# Embebidos.net
KiCad netlist of a schematic drawn in Altium Designer
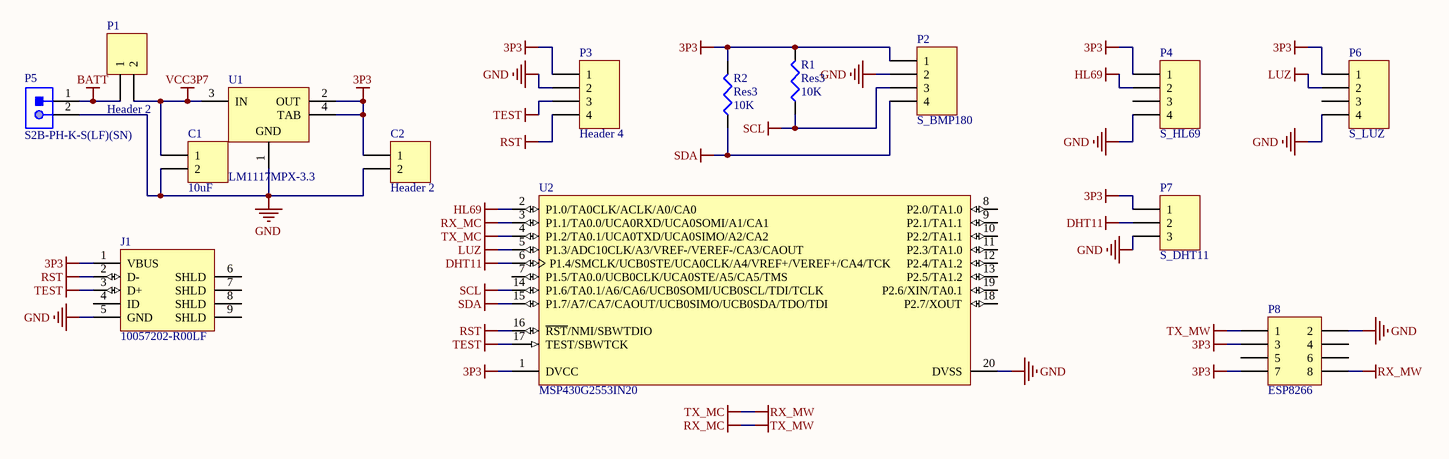
[diagram p0: Embebidos.SchDoc]

(export (version "E")
  (design (tool "Eeschema 10.0.6"))
  (components
    (comp (ref "C1")
      (value "10uF")
      (footprint "HDR1X2")
      (description "Header, 2-Pin")
      (fields (field (name "PUBLISHER") "Altium Limited"))
      (libsource (lib "Miscellaneous Connectors") (part "Header 2"))
    )
    (comp (ref "C2")
      (value "Header 2")
      (footprint "HDR1X2")
      (description "Header, 2-Pin")
      (fields (field (name "PUBLISHER") "Altium Limited"))
      (libsource (lib "Miscellaneous Connectors") (part "Header 2"))
    )
    (comp (ref "J1")
      (value "10057202-R00LF")
      (footprint "FCI-10057202-R00LF_V")
      (description "Connector Mini USB, Right Angle, Receptacle, Type B")
      (fields (field (name "MANUFACTURER") "FCI Electronics"))
      (libsource (lib "Altium Content Vault") (part "CMP-0397-00001-1"))
    )
    (comp (ref "P1")
      (value "Header 2")
      (footprint "HDR1X2")
      (description "Header, 2-Pin")
      (fields (field (name "PUBLISHER") "Altium Limited"))
      (libsource (lib "") (part "Header 2_1"))
    )
    (comp (ref "P2")
      (value "S_BMP180")
      (footprint "HDR1X4")
      (description "Header, 4-Pin")
      (fields (field (name "PUBLISHER") "Altium Limited"))
      (libsource (lib "Miscellaneous Connectors") (part "Header 4"))
    )
    (comp (ref "P3")
      (value "Header 4")
      (footprint "HDR1X4")
      (description "Header, 4-Pin")
      (fields (field (name "PUBLISHER") "Altium Limited"))
      (libsource (lib "Miscellaneous Connectors") (part "Header 4"))
    )
    (comp (ref "P4")
      (value "S_HL69")
      (footprint "HDR1X4")
      (description "Header, 4-Pin")
      (fields (field (name "PUBLISHER") "Altium Limited"))
      (libsource (lib "Miscellaneous Connectors") (part "Header 4"))
    )
    (comp (ref "P5")
      (value "S2B-PH-K-S(LF)(SN)")
      (footprint "JST-S2B-PH-K-S_V")
      (fields (field (name "TOLERANCE") "20%"))
      (libsource (lib "Altium Content Vault") (part "CMP-1755-00004-1"))
    )
    (comp (ref "P6")
      (value "S_LUZ")
      (footprint "HDR1X4")
      (description "Header, 4-Pin")
      (fields (field (name "PUBLISHER") "Altium Limited"))
      (libsource (lib "Miscellaneous Connectors") (part "Header 4"))
    )
    (comp (ref "P7")
      (value "S_DHT11")
      (footprint "HDR1X3")
      (description "Header, 3-Pin")
      (fields (field (name "PUBLISHER") "Altium Limited"))
      (libsource (lib "Miscellaneous Connectors") (part "Header 3"))
    )
    (comp (ref "P8")
      (value "ESP8266")
      (footprint "HDR2X4")
      (description "Header, 4-Pin, Dual row")
      (fields (field (name "PUBLISHER") "Altium Limited"))
      (libsource (lib "Miscellaneous Connectors") (part "Header 4X2"))
    )
    (comp (ref "R1")
      (value "Res3")
      (footprint "J1-0603")
      (description "Resistor")
      (fields (field (name "ALTIUM_VALUE") "10K") (field (name "PUBLISHER") "Altium Limited"))
      (libsource (lib "Miscellaneous Devices") (part "Res3"))
    )
    (comp (ref "R2")
      (value "Res3")
      (footprint "J1-0603")
      (description "Resistor")
      (fields (field (name "ALTIUM_VALUE") "10K") (field (name "PUBLISHER") "Altium Limited"))
      (libsource (lib "Miscellaneous Devices") (part "Res3"))
    )
    (comp (ref "U1")
      (value "LM1117MPX-3.3")
      (footprint "DCY0004A_N")
      (description "800mA Low-Dropout Linear Regulator, 4-pin SOT-223")
      (fields (field (name "MANUFACTURER") "Texas Instruments"))
      (libsource (lib "Altium Content Vault") (part "PM-REG-LM1086-SOT4"))
    )
    (comp (ref "U2")
      (value "MSP430G2553IN20")
      (footprint "N0020A")
      (fields (field (name "MANUFACTURER") "Texas Instruments"))
      (libsource (lib "Altium Content Vault") (part "CMP-0365-00184-2"))
    )
  )
  (nets
    (net (code "1") (name "3P3") (class "Default")
      (node (ref "C2") (pin "1") (pinfunction "1_1") (pintype "passive"))
      (node (ref "J1") (pin "1") (pinfunction "VBUS_1") (pintype "power_in"))
      (node (ref "P2") (pin "1") (pinfunction "1_1") (pintype "passive"))
      (node (ref "P3") (pin "1") (pinfunction "1_1") (pintype "passive"))
      (node (ref "P4") (pin "1") (pinfunction "1_1") (pintype "passive"))
      (node (ref "P6") (pin "1") (pinfunction "1_1") (pintype "passive"))
      (node (ref "P7") (pin "1") (pinfunction "1_1") (pintype "passive"))
      (node (ref "P8") (pin "3") (pinfunction "3_3") (pintype "passive"))
      (node (ref "P8") (pin "7") (pinfunction "7_7") (pintype "passive"))
      (node (ref "R1") (pin "2") (pinfunction "2_2") (pintype "passive"))
      (node (ref "R2") (pin "2") (pinfunction "2_2") (pintype "passive"))
      (node (ref "U1") (pin "2") (pinfunction "OUT_2") (pintype "power_in"))
      (node (ref "U1") (pin "4") (pinfunction "TAB_4") (pintype "power_in"))
      (node (ref "U2") (pin "1") (pinfunction "DVCC_1") (pintype "power_in"))
    )
    (net (code "2") (name "BATT") (class "Default")
      (node (ref "P1") (pin "1") (pinfunction "1_1") (pintype "passive"))
      (node (ref "P5") (pin "1") (pinfunction "1_1") (pintype "passive"))
    )
    (net (code "3") (name "DHT11") (class "Default")
      (node (ref "P7") (pin "2") (pinfunction "2_2") (pintype "passive"))
      (node (ref "U2") (pin "6") (pinfunction "P1.4/SMCLK/UCB0STE/UCA0CLK/A4/VREF+/VEREF+/CA4/TCK_6") (pintype "bidirectional"))
    )
    (net (code "4") (name "GND") (class "Default")
      (node (ref "C1") (pin "2") (pinfunction "2_2") (pintype "passive"))
      (node (ref "C2") (pin "2") (pinfunction "2_2") (pintype "passive"))
      (node (ref "J1") (pin "5") (pinfunction "GND_5") (pintype "power_in"))
      (node (ref "P2") (pin "2") (pinfunction "2_2") (pintype "passive"))
      (node (ref "P3") (pin "2") (pinfunction "2_2") (pintype "passive"))
      (node (ref "P4") (pin "4") (pinfunction "4_4") (pintype "passive"))
      (node (ref "P5") (pin "2") (pinfunction "2_2") (pintype "passive"))
      (node (ref "P6") (pin "4") (pinfunction "4_4") (pintype "passive"))
      (node (ref "P7") (pin "3") (pinfunction "3_3") (pintype "passive"))
      (node (ref "P8") (pin "2") (pinfunction "2_2") (pintype "passive"))
      (node (ref "U1") (pin "1") (pinfunction "GND_1") (pintype "power_in"))
      (node (ref "U2") (pin "20") (pinfunction "DVSS_20") (pintype "power_in"))
    )
    (net (code "5") (name "HL69") (class "Default")
      (node (ref "P4") (pin "2") (pinfunction "2_2") (pintype "passive"))
      (node (ref "U2") (pin "2") (pinfunction "P1.0/TA0CLK/ACLK/A0/CA0_2") (pintype "bidirectional"))
    )
    (net (code "6") (name "LUZ") (class "Default")
      (node (ref "P6") (pin "2") (pinfunction "2_2") (pintype "passive"))
      (node (ref "U2") (pin "5") (pinfunction "P1.3/ADC10CLK/A3/VREF-/VEREF-/CA3/CAOUT_5") (pintype "bidirectional"))
    )
    (net (code "7") (name "RST") (class "Default")
      (node (ref "J1") (pin "2") (pinfunction "D-_2") (pintype "bidirectional"))
      (node (ref "P3") (pin "4") (pinfunction "4_4") (pintype "passive"))
      (node (ref "U2") (pin "16") (pinfunction "~{RST}/NMI/SBWTDIO_16") (pintype "bidirectional"))
    )
    (net (code "8") (name "RX_MC") (class "Default")
      (node (ref "P8") (pin "1") (pinfunction "1_1") (pintype "passive"))
      (node (ref "U2") (pin "3") (pinfunction "P1.1/TA0.0/UCA0RXD/UCA0SOMI/A1/CA1_3") (pintype "bidirectional"))
    )
    (net (code "9") (name "RX_MW") (class "Default")
      (node (ref "P8") (pin "8") (pinfunction "8_8") (pintype "passive"))
      (node (ref "U2") (pin "4") (pinfunction "P1.2/TA0.1/UCA0TXD/UCA0SIMO/A2/CA2_4") (pintype "bidirectional"))
    )
    (net (code "10") (name "SCL") (class "Default")
      (node (ref "P2") (pin "3") (pinfunction "3_3") (pintype "passive"))
      (node (ref "R1") (pin "1") (pinfunction "1_1") (pintype "passive"))
      (node (ref "U2") (pin "14") (pinfunction "P1.6/TA0.1/A6/CA6/UCB0SOMI/UCB0SCL/TDI/TCLK_14") (pintype "bidirectional"))
    )
    (net (code "11") (name "SDA") (class "Default")
      (node (ref "P2") (pin "4") (pinfunction "4_4") (pintype "passive"))
      (node (ref "R2") (pin "1") (pinfunction "1_1") (pintype "passive"))
      (node (ref "U2") (pin "15") (pinfunction "P1.7/A7/CA7/CAOUT/UCB0SIMO/UCB0SDA/TDO/TDI_15") (pintype "bidirectional"))
    )
    (net (code "12") (name "TEST") (class "Default")
      (node (ref "J1") (pin "3") (pinfunction "D+_3") (pintype "bidirectional"))
      (node (ref "P3") (pin "3") (pinfunction "3_3") (pintype "passive"))
      (node (ref "U2") (pin "17") (pinfunction "TEST/SBWTCK_17") (pintype "input"))
    )
    (net (code "13") (name "VCC3P7") (class "Default")
      (node (ref "C1") (pin "1") (pinfunction "1_1") (pintype "passive"))
      (node (ref "P1") (pin "2") (pinfunction "2_2") (pintype "passive"))
      (node (ref "U1") (pin "3") (pinfunction "IN_3") (pintype "power_in"))
    )
    (net (code "14") (name "unconnected-(J1-ID-Pad4)") (class "Default")
      (node (ref "J1") (pin "4") (pinfunction "ID_4") (pintype "passive"))
    )
    (net (code "15") (name "unconnected-(J1-SHLD-Pad6)") (class "Default")
      (node (ref "J1") (pin "6") (pinfunction "SHLD_6") (pintype "passive"))
    )
    (net (code "16") (name "unconnected-(J1-SHLD-Pad7)") (class "Default")
      (node (ref "J1") (pin "7") (pinfunction "SHLD_7") (pintype "passive"))
    )
    (net (code "17") (name "unconnected-(J1-SHLD-Pad8)") (class "Default")
      (node (ref "J1") (pin "8") (pinfunction "SHLD_8") (pintype "passive"))
    )
    (net (code "18") (name "unconnected-(J1-SHLD-Pad9)") (class "Default")
      (node (ref "J1") (pin "9") (pinfunction "SHLD_9") (pintype "passive"))
    )
    (net (code "19") (name "unconnected-(P4-Pad3)") (class "Default")
      (node (ref "P4") (pin "3") (pinfunction "3_3") (pintype "passive"))
    )
    (net (code "20") (name "unconnected-(P6-Pad3)") (class "Default")
      (node (ref "P6") (pin "3") (pinfunction "3_3") (pintype "passive"))
    )
    (net (code "21") (name "unconnected-(P8-Pad4)") (class "Default")
      (node (ref "P8") (pin "4") (pinfunction "4_4") (pintype "passive"))
    )
    (net (code "22") (name "unconnected-(P8-Pad5)") (class "Default")
      (node (ref "P8") (pin "5") (pinfunction "5_5") (pintype "passive"))
    )
    (net (code "23") (name "unconnected-(P8-Pad6)") (class "Default")
      (node (ref "P8") (pin "6") (pinfunction "6_6") (pintype "passive"))
    )
    (net (code "24") (name "unconnected-(U2-P1.5{slash}TA0.0{slash}UCB0CLK{slash}UCA0STE{slash}A5{slash}CA5{slash}TMS-Pad7)") (class "Default")
      (node (ref "U2") (pin "7") (pinfunction "P1.5/TA0.0/UCB0CLK/UCA0STE/A5/CA5/TMS_7") (pintype "bidirectional"))
    )
    (net (code "25") (name "unconnected-(U2-P2.0{slash}TA1.0-Pad8)") (class "Default")
      (node (ref "U2") (pin "8") (pinfunction "P2.0/TA1.0_8") (pintype "bidirectional"))
    )
    (net (code "26") (name "unconnected-(U2-P2.1{slash}TA1.1-Pad9)") (class "Default")
      (node (ref "U2") (pin "9") (pinfunction "P2.1/TA1.1_9") (pintype "bidirectional"))
    )
    (net (code "27") (name "unconnected-(U2-P2.2{slash}TA1.1-Pad10)") (class "Default")
      (node (ref "U2") (pin "10") (pinfunction "P2.2/TA1.1_10") (pintype "bidirectional"))
    )
    (net (code "28") (name "unconnected-(U2-P2.3{slash}TA1.0-Pad11)") (class "Default")
      (node (ref "U2") (pin "11") (pinfunction "P2.3/TA1.0_11") (pintype "bidirectional"))
    )
    (net (code "29") (name "unconnected-(U2-P2.4{slash}TA1.2-Pad12)") (class "Default")
      (node (ref "U2") (pin "12") (pinfunction "P2.4/TA1.2_12") (pintype "bidirectional"))
    )
    (net (code "30") (name "unconnected-(U2-P2.5{slash}TA1.2-Pad13)") (class "Default")
      (node (ref "U2") (pin "13") (pinfunction "P2.5/TA1.2_13") (pintype "bidirectional"))
    )
    (net (code "31") (name "unconnected-(U2-P2.6{slash}XIN{slash}TA0.1-Pad19)") (class "Default")
      (node (ref "U2") (pin "19") (pinfunction "P2.6/XIN/TA0.1_19") (pintype "bidirectional"))
    )
    (net (code "32") (name "unconnected-(U2-P2.7{slash}XOUT-Pad18)") (class "Default")
      (node (ref "U2") (pin "18") (pinfunction "P2.7/XOUT_18") (pintype "bidirectional"))
    )
  )
)
